# Sheet1.net
KiCad netlist of a schematic drawn in Altium Designer
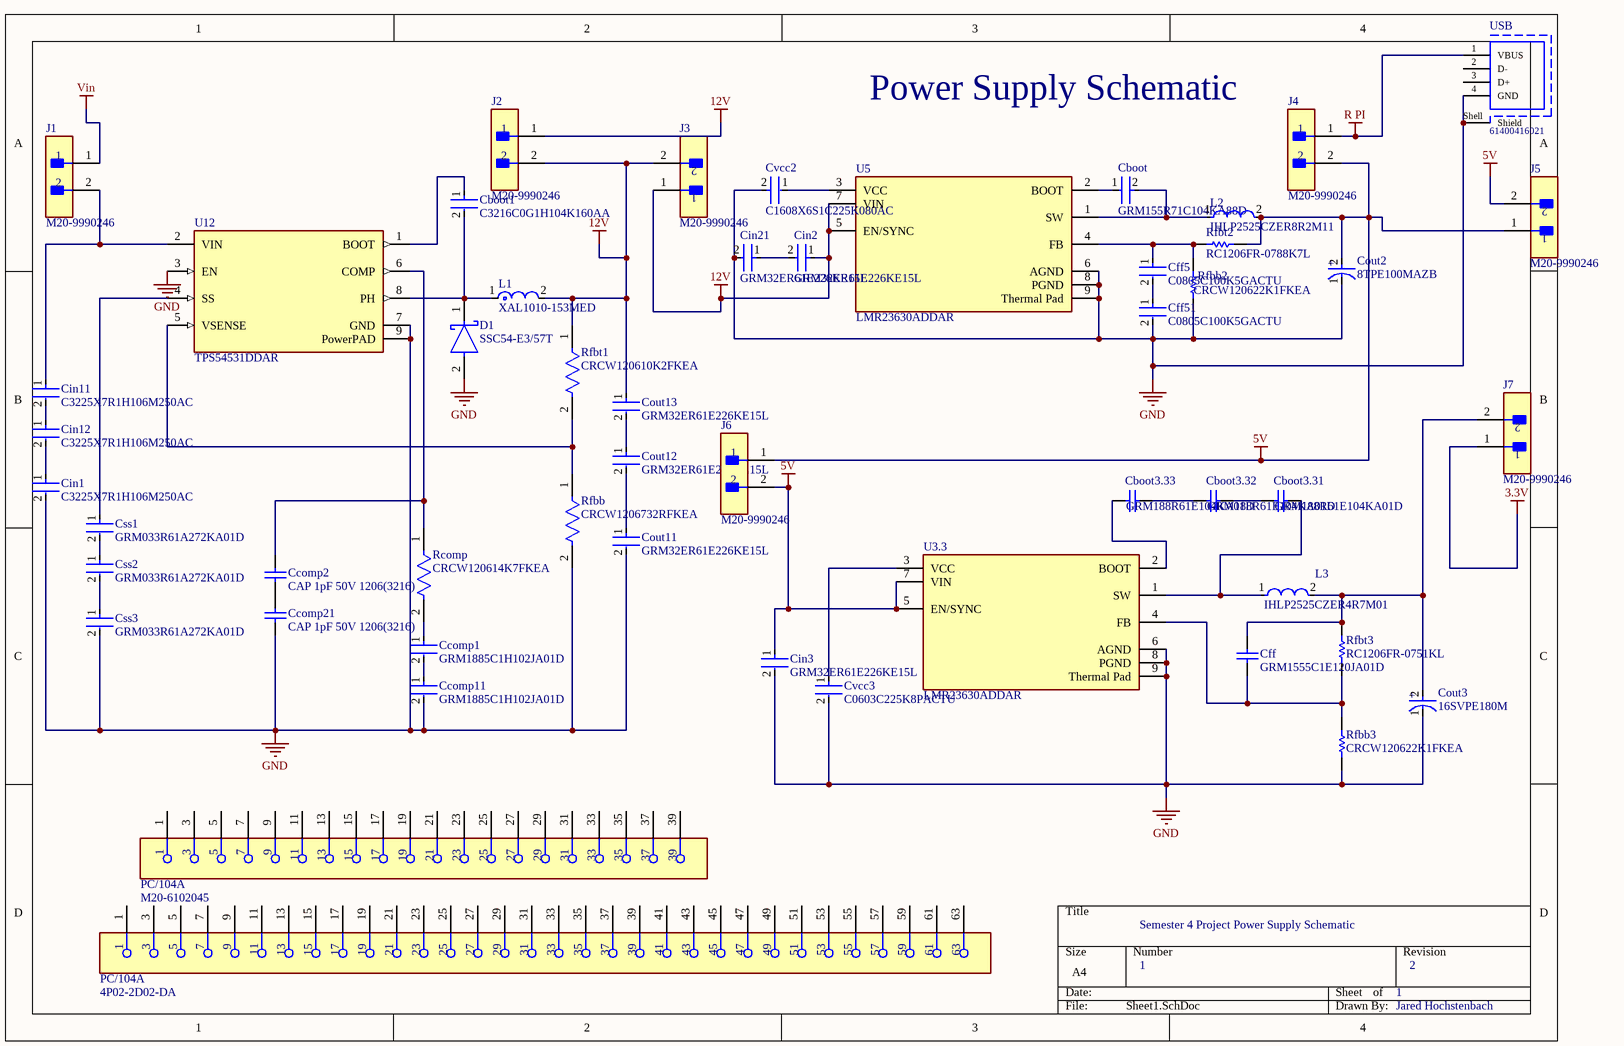
[diagram p0: Sheet1.SchDoc]

(export (version "E")
  (design (tool "Eeschema 10.0.6"))
  (components
    (comp (ref "Cboot")
      (value "GRM155R71C104KA88D")
      (footprint "FP-GRM15-MFG")
      (description "CAP CER 0.1UF 16V X7R 0402")
      (fields
        (field (name "TOLERANCE") "10%")
        (field (name "OCTOPART") "https://octopart.com/grm155r71c104ka88d-murata-196880")
      )
      (libsource (lib "Altium Content Vault") (part "236180d848d6139a670b325ea6854c9"))
    )
    (comp (ref "Cboot1")
      (value "C3216C0G1H104K160AA")
      (footprint "FP-C3216-160-0_2-IPC_C")
      (description "Multilayer Ceramic Capacitors 100nF ±10% 50V C0G SMD 1206")
      (fields (field (name "TOLERANCE") "10%"))
      (libsource (lib "Altium Content Vault") (part "11868f565c42a9108669ba33697ecf6"))
    )
    (comp (ref "Cboot3.31")
      (value "GRM188R61E104KA01D")
      (footprint "CAPC1608X90X35NL10T15")
      (fields (field (name "MANUFACTURER") "Murata"))
      (libsource (lib "Altium Content Vault") (part "CAP"))
    )
    (comp (ref "Cboot3.32")
      (value "GRM188R61E104KA01D")
      (footprint "CAPC1608X90X35NL10T15")
      (fields (field (name "MANUFACTURER") "Murata"))
      (libsource (lib "Altium Content Vault") (part "CAP"))
    )
    (comp (ref "Cboot3.33")
      (value "GRM188R61E104KA01D")
      (footprint "CAPC1608X90X35NL10T15")
      (fields (field (name "MANUFACTURER") "Murata"))
      (libsource (lib "Altium Content Vault") (part "CAP"))
    )
    (comp (ref "Ccomp1")
      (value "GRM1885C1H102JA01D")
      (footprint "FP-GRM188-0_1-e0_2_0_5-IPC_C")
      (description "Chip Multilayer Ceramic Capacitors for General Purpose, 0603, 1000pF, C0G, 30ppm/°C, 5%, 50V")
      (fields (field (name "TOLERANCE") "5%") (field (name "VOLTAGE") "50V"))
      (libsource (lib "Altium Content Vault") (part "11868f565c42a9108669ba33697ecf6"))
    )
    (comp (ref "Ccomp2")
      (value "CAP 1pF 50V 1206(3216)")
      (footprint "CAPC1206(3216)100_N")
      (description "CAP 1pF 50V ±0.25pF 1206 (3216 Metric) Thickness 1mm SMD")
      (fields (field (name "TOLERANCE") "Â±0.25pF"))
      (libsource (lib "Altium Content Vault") (part "CAP"))
    )
    (comp (ref "Ccomp11")
      (value "GRM1885C1H102JA01D")
      (footprint "FP-GRM188-0_1-e0_2_0_5-IPC_C")
      (description "Chip Multilayer Ceramic Capacitors for General Purpose, 0603, 1000pF, C0G, 30ppm/°C, 5%, 50V")
      (fields (field (name "TOLERANCE") "5%") (field (name "VOLTAGE") "50V"))
      (libsource (lib "Altium Content Vault") (part "11868f565c42a9108669ba33697ecf6"))
    )
    (comp (ref "Ccomp21")
      (value "CAP 1pF 50V 1206(3216)")
      (footprint "CAPC1206(3216)100_N")
      (description "CAP 1pF 50V ±0.25pF 1206 (3216 Metric) Thickness 1mm SMD")
      (fields (field (name "TOLERANCE") "Â±0.25pF"))
      (libsource (lib "Altium Content Vault") (part "CAP"))
    )
    (comp (ref "Cff")
      (value "GRM1555C1E120JA01D")
      (footprint "CAPC1005X55X25LL05T10")
      (fields (field (name "MANUFACTURER") "Murata"))
      (libsource (lib "Altium Content Vault") (part "CAP"))
    )
    (comp (ref "Cff5")
      (value "C0805C100K5GACTU")
      (footprint "FP-C0805C-DN-MFG")
      (description "CAP CER 10PF 50V 10% NP0 0805")
      (fields
        (field (name "MANUFACTURER") "KEMET")
        (field (name "OCTOPART") "https://octopart.com/c0805c100k5gactu-kemet-8089747")
      )
      (libsource (lib "Altium Content Vault") (part "b4654b650e69147ec39a6b967a45e02"))
    )
    (comp (ref "Cff51")
      (value "C0805C100K5GACTU")
      (footprint "FP-C0805C-DN-MFG")
      (description "CAP CER 10PF 50V 10% NP0 0805")
      (fields
        (field (name "MANUFACTURER") "KEMET")
        (field (name "OCTOPART") "https://octopart.com/c0805c100k5gactu-kemet-8089747")
      )
      (libsource (lib "Altium Content Vault") (part "b4654b650e69147ec39a6b967a45e02"))
    )
    (comp (ref "Cin1")
      (value "C3225X7R1H106M250AC")
      (footprint "FP-C3225-250-0_4-MFG")
      (description "Multilayer Ceramic Capacitors 10uF ±20% 50V X7R SMD 1210")
      (fields (field (name "TOLERANCE") "20%"))
      (libsource (lib "Altium Content Vault") (part "02cd4be3c70576c341d710602a673aa"))
    )
    (comp (ref "Cin2")
      (value "GRM32ER61E226KE15L")
      (footprint "FP-GRM32-MFG")
      (description "CAP CER 22UF 25V X5R 1210")
      (fields
        (field (name "TOLERANCE") "10%")
        (field (name "MANUFACTURER") "Murata Electronics North America")
      )
      (libsource (lib "Altium Content Vault") (part "11868f565c42a9108669ba33697ecf6"))
    )
    (comp (ref "Cin3")
      (value "GRM32ER61E226KE15L")
      (footprint "FP-GRM32-MFG")
      (description "CAP CER 22UF 25V X5R 1210")
      (fields
        (field (name "TOLERANCE") "10%")
        (field (name "MANUFACTURER") "Murata Electronics North America")
      )
      (libsource (lib "Altium Content Vault") (part "11868f565c42a9108669ba33697ecf6"))
    )
    (comp (ref "Cin11")
      (value "C3225X7R1H106M250AC")
      (footprint "FP-C3225-250-0_4-MFG")
      (description "Multilayer Ceramic Capacitors 10uF ±20% 50V X7R SMD 1210")
      (fields (field (name "TOLERANCE") "20%"))
      (libsource (lib "Altium Content Vault") (part "02cd4be3c70576c341d710602a673aa"))
    )
    (comp (ref "Cin12")
      (value "C3225X7R1H106M250AC")
      (footprint "FP-C3225-250-0_4-MFG")
      (description "Multilayer Ceramic Capacitors 10uF ±20% 50V X7R SMD 1210")
      (fields (field (name "TOLERANCE") "20%"))
      (libsource (lib "Altium Content Vault") (part "02cd4be3c70576c341d710602a673aa"))
    )
    (comp (ref "Cin21")
      (value "GRM32ER61E226KE15L")
      (footprint "FP-GRM32-MFG")
      (description "CAP CER 22UF 25V X5R 1210")
      (fields
        (field (name "TOLERANCE") "10%")
        (field (name "MANUFACTURER") "Murata Electronics North America")
      )
      (libsource (lib "Altium Content Vault") (part "11868f565c42a9108669ba33697ecf6"))
    )
    (comp (ref "Cout2")
      (value "8TPE100MAZB")
      (footprint "FP-POSCAP-B2-MFG")
      (description "Molded Tantalum Polymer Capacitor 100uF 20% 8V life 1000Hours SMD 1411")
      (fields (field (name "TOLERANCE") "20%") (field (name "VOLTAGE") "8V"))
      (libsource (lib "Altium Content Vault") (part "cf48714ba7e38822c1575c7ec0b6d1f"))
    )
    (comp (ref "Cout3")
      (value "16SVPE180M")
      (footprint "FP-OS-CON-SMT-C10-MFG")
      (description "CAP ALUM POLY 180UF 20% 16V SMD")
      (fields (field (name "VOLTAGE") "16V") (field (name "TOLERANCE") "20%"))
      (libsource (lib "Altium Content Vault") (part "203bc49f2ac43e59fd269a8c329ed05"))
    )
    (comp (ref "Cout11")
      (value "GRM32ER61E226KE15L")
      (footprint "FP-GRM32-MFG")
      (description "CAP CER 22UF 25V X5R 1210")
      (fields
        (field (name "TOLERANCE") "10%")
        (field (name "MANUFACTURER") "Murata Electronics North America")
      )
      (libsource (lib "Altium Content Vault") (part "11868f565c42a9108669ba33697ecf6"))
    )
    (comp (ref "Cout12")
      (value "GRM32ER61E226KE15L")
      (footprint "FP-GRM32-MFG")
      (description "CAP CER 22UF 25V X5R 1210")
      (fields
        (field (name "TOLERANCE") "10%")
        (field (name "MANUFACTURER") "Murata Electronics North America")
      )
      (libsource (lib "Altium Content Vault") (part "11868f565c42a9108669ba33697ecf6"))
    )
    (comp (ref "Cout13")
      (value "GRM32ER61E226KE15L")
      (footprint "FP-GRM32-MFG")
      (description "CAP CER 22UF 25V X5R 1210")
      (fields
        (field (name "TOLERANCE") "10%")
        (field (name "MANUFACTURER") "Murata Electronics North America")
      )
      (libsource (lib "Altium Content Vault") (part "11868f565c42a9108669ba33697ecf6"))
    )
    (comp (ref "Css1")
      (value "GRM033R61A272KA01D")
      (footprint "FP-GRM033-0_03-IPC_B")
      (description "Chip Multilayer Ceramic Capacitors for General Purpose, 0201, 2700pF, X5R, 15%, 10%, 10V")
      (fields (field (name "TOLERANCE") "10%"))
      (libsource (lib "Altium Content Vault") (part "b4654b650e69147ec39a6b967a45e02"))
    )
    (comp (ref "Css2")
      (value "GRM033R61A272KA01D")
      (footprint "FP-GRM033-0_03-IPC_B")
      (description "Chip Multilayer Ceramic Capacitors for General Purpose, 0201, 2700pF, X5R, 15%, 10%, 10V")
      (fields (field (name "TOLERANCE") "10%"))
      (libsource (lib "Altium Content Vault") (part "b4654b650e69147ec39a6b967a45e02"))
    )
    (comp (ref "Css3")
      (value "GRM033R61A272KA01D")
      (footprint "FP-GRM033-0_03-IPC_B")
      (description "Chip Multilayer Ceramic Capacitors for General Purpose, 0201, 2700pF, X5R, 15%, 10%, 10V")
      (fields (field (name "TOLERANCE") "10%"))
      (libsource (lib "Altium Content Vault") (part "b4654b650e69147ec39a6b967a45e02"))
    )
    (comp (ref "Cvcc2")
      (value "C1608X6S1C225K080AC")
      (footprint "FP-C1608-080-0_1-IPC_A")
      (description "Multilayer Ceramic Capacitors 2.2μF ±10% 16V X6S SMD 0603")
      (fields (field (name "TOLERANCE") "10%"))
      (libsource (lib "Altium Content Vault") (part "236180d848d6139a670b325ea6854c9"))
    )
    (comp (ref "Cvcc3")
      (value "C0603C225K8PACTU")
      (footprint "FP-C0603C225K8PACTU-MFG")
      (description "CAP CER 2.2UF 10V X5R 0603")
      (fields (field (name "VOLTAGE") "10V") (field (name "TOLERANCE") "10%"))
      (libsource (lib "Altium Content Vault") (part "e9c51b7dd13d4faca003ae77663ab08"))
    )
    (comp (ref "D1")
      (value "SSC54-E3/57T")
      (footprint "FP-95402-MFG")
      (description "DIODE SCHOTTKY 40V 5A DO214AB")
      (fields
        (field (name "OCTOPART") "https://octopart.com/ssc54-e3%2F57t-vishay-39552944")
        (field (name "MANUFACTURER") "Vishay")
      )
      (libsource (lib "Altium Content Vault") (part "1d6ec82d83fb6aee721767c19dac4b9"))
    )
    (comp (ref "J1")
      (value "M20-9990246")
      (footprint "FP-M20-9990246-MFG")
      (description "CONN HEADER VERT 2POS 2.54MM")
      (fields
        (field (name "OCTOPART") "https://octopart.com/m20-9990246-harwin-2590635")
        (field (name "MANUFACTURER") "Harwin")
      )
      (libsource (lib "Altium Content Vault") (part "3bc925449376181038e59eaffc5286c"))
    )
    (comp (ref "J2")
      (value "M20-9990246")
      (footprint "FP-M20-9990246-MFG")
      (description "CONN HEADER VERT 2POS 2.54MM")
      (fields
        (field (name "OCTOPART") "https://octopart.com/m20-9990246-harwin-2590635")
        (field (name "MANUFACTURER") "Harwin")
      )
      (libsource (lib "Altium Content Vault") (part "3bc925449376181038e59eaffc5286c"))
    )
    (comp (ref "J3")
      (value "M20-9990246")
      (footprint "FP-M20-9990246-MFG")
      (description "CONN HEADER VERT 2POS 2.54MM")
      (fields
        (field (name "OCTOPART") "https://octopart.com/m20-9990246-harwin-2590635")
        (field (name "MANUFACTURER") "Harwin")
      )
      (libsource (lib "") (part "3bc925449376181038e59eaffc5286c_1"))
    )
    (comp (ref "J4")
      (value "M20-9990246")
      (footprint "FP-M20-9990246-MFG")
      (description "CONN HEADER VERT 2POS 2.54MM")
      (fields
        (field (name "OCTOPART") "https://octopart.com/m20-9990246-harwin-2590635")
        (field (name "MANUFACTURER") "Harwin")
      )
      (libsource (lib "Altium Content Vault") (part "3bc925449376181038e59eaffc5286c"))
    )
    (comp (ref "J5")
      (value "M20-9990246")
      (footprint "FP-M20-9990246-MFG")
      (description "CONN HEADER VERT 2POS 2.54MM")
      (fields
        (field (name "OCTOPART") "https://octopart.com/m20-9990246-harwin-2590635")
        (field (name "MANUFACTURER") "Harwin")
      )
      (libsource (lib "") (part "3bc925449376181038e59eaffc5286c_1"))
    )
    (comp (ref "J6")
      (value "M20-9990246")
      (footprint "FP-M20-9990246-MFG")
      (description "CONN HEADER VERT 2POS 2.54MM")
      (fields
        (field (name "OCTOPART") "https://octopart.com/m20-9990246-harwin-2590635")
        (field (name "MANUFACTURER") "Harwin")
      )
      (libsource (lib "Altium Content Vault") (part "3bc925449376181038e59eaffc5286c"))
    )
    (comp (ref "J7")
      (value "M20-9990246")
      (footprint "FP-M20-9990246-MFG")
      (description "CONN HEADER VERT 2POS 2.54MM")
      (fields
        (field (name "OCTOPART") "https://octopart.com/m20-9990246-harwin-2590635")
        (field (name "MANUFACTURER") "Harwin")
      )
      (libsource (lib "") (part "3bc925449376181038e59eaffc5286c_1"))
    )
    (comp (ref "L1")
      (value "XAL1010-153MED")
      (footprint "FP-XAL1010-MFG")
      (description "Fixed Inductors 15uH Shld 20% 13.8A 18.6mOhms AECQ2")
      (fields (field (name "TOLERANCE") "20%"))
      (libsource (lib "Altium Content Vault") (part "4cc4b267dca4c8e51f7102f422741d8"))
    )
    (comp (ref "L2")
      (value "IHLP2525CZER8R2M11")
      (footprint "FP-IHLP-2525CZ-FP_2_413x3-MFG")
      (description "Commercial Inductors, Low DCR Series 8.2uH 5A 54.9mΩ 20%")
      (fields (field (name "TOLERANCE") "20%"))
      (libsource (lib "Altium Content Vault") (part "725321dda6339637d4d059423bc1c3c"))
    )
    (comp (ref "L3")
      (value "IHLP2525CZER4R7M01")
      (footprint "FP-IHLP-2525CZ-FP_2_413x3-MFG")
      (description "Commercial Inductors, High Saturation Series 4.7uH 5.5A 40mΩ 20%")
      (fields (field (name "TOLERANCE") "20%"))
      (libsource (lib "Altium Content Vault") (part "725321dda6339637d4d059423bc1c3c"))
    )
    (comp (ref "PC/104")
      (value "4P02-2D02-DA")
      (footprint "FP-4P02-2D02-DA-MFG")
      (description "CONN STKTHRU PC/104 64POS PCB")
      (libsource (lib "Altium Content Vault") (part "e49c52f63edff4b5683a6d6b4db1caa"))
    )
    (comp (ref "Rcomp")
      (value "CRCW120614K7FKEA")
      (footprint "FP-CRCW1206-e3-MFG")
      (description "RES Thick Film, 14.7kΩ, 1%, 0.25W, 100ppm/°C, 1206")
      (fields (field (name "TOLERANCE") "1%"))
      (libsource (lib "Altium Content Vault") (part "1029c3af85768c4190bb7ad29bc67b5"))
    )
    (comp (ref "Rfbb")
      (value "CRCW1206732RFKEA")
      (footprint "FP-CRCW1206-e3-IPC_B")
      (description "RES Thick Film, 732Ω, 1%, 0.25W, 100ppm/°C, 1206")
      (fields (field (name "TOLERANCE") "1%"))
      (libsource (lib "Altium Content Vault") (part "1029c3af85768c4190bb7ad29bc67b5"))
    )
    (comp (ref "Rfbb2")
      (value "CRCW120622K1FKEA")
      (footprint "RESC3216X60X45ML10T20")
      (fields (field (name "MANUFACTURER") "Vishay Dale"))
      (libsource (lib "Altium Content Vault") (part "RES"))
    )
    (comp (ref "Rfbb3")
      (value "CRCW120622K1FKEA")
      (footprint "RESC3216X60X45ML10T20")
      (fields (field (name "MANUFACTURER") "Vishay Dale"))
      (libsource (lib "Altium Content Vault") (part "RES"))
    )
    (comp (ref "Rfbt1")
      (value "CRCW120610K2FKEA")
      (footprint "FP-CRCW1206-e3-MFG")
      (description "RES Thick Film, 10.2kΩ, 1%, 0.25W, 100ppm/°C, 1206")
      (fields (field (name "TOLERANCE") "1%"))
      (libsource (lib "Altium Content Vault") (part "1029c3af85768c4190bb7ad29bc67b5"))
    )
    (comp (ref "Rfbt2")
      (value "RC1206FR-0788K7L")
      (footprint "RESC3116X65X40LL10T20")
      (fields (field (name "MANUFACTURER") "Yageo"))
      (libsource (lib "Altium Content Vault") (part "RES"))
    )
    (comp (ref "Rfbt3")
      (value "RC1206FR-0751KL")
      (footprint "RESC3116X65X40NL10T20")
      (fields (field (name "MANUFACTURER") "Yageo"))
      (libsource (lib "Altium Content Vault") (part "RES"))
    )
    (comp (ref "U3.3")
      (value "LMR23630ADDAR")
      (footprint "FP-DDA0008E-MFG")
      (description "IC REG BUCK ADJUSTABLE 3A 8SOPWR")
      (libsource (lib "Altium Content Vault") (part "58cfab92c18b1e9607657e2a6918072"))
    )
    (comp (ref "U5")
      (value "LMR23630ADDAR")
      (footprint "FP-DDA0008E-MFG")
      (description "IC REG BUCK ADJUSTABLE 3A 8SOPWR")
      (libsource (lib "Altium Content Vault") (part "58cfab92c18b1e9607657e2a6918072"))
    )
    (comp (ref "U12")
      (value "TPS54531DDAR")
      (footprint "FP-DDA0008E-MFG")
      (description "IC REG BUCK ADJUSTABLE 5A 8SOPWR")
      (libsource (lib "Altium Content Vault") (part "0ba9c67d8848e7a3c062535a516a02c"))
    )
    (comp (ref "USB")
      (value "61400416021")
      (footprint "61400416021")
      (description "USB 2.0 Type A Receptacle WR-COM, Horizontal, THT")
      (fields (field (name "MANUFACTURER") "Wurth Elektronik") (field (name "PUBLISHER") "WurthElektronik"))
      (libsource (lib "Altium Content Vault") (part "WE-USB-4-1SHLD"))
    )
  )
  (nets
    (net (code "1") (name "3.3V") (class "Default")
      (node (ref "J7") (pin "1") (pinfunction "1_1") (pintype "passive"))
    )
    (net (code "2") (name "5V") (class "Default")
      (node (ref "Cin3") (pin "1") (pinfunction "1_1") (pintype "passive"))
      (node (ref "Cout2") (pin "2") (pinfunction "A_2") (pintype "passive"))
      (node (ref "J4") (pin "2") (pinfunction "2_2") (pintype "passive"))
      (node (ref "J5") (pin "1") (pinfunction "1_1") (pintype "passive"))
      (node (ref "J5") (pin "2") (pinfunction "2_2") (pintype "passive"))
      (node (ref "J6") (pin "1") (pinfunction "1_1") (pintype "passive"))
      (node (ref "J6") (pin "2") (pinfunction "2_2") (pintype "passive"))
      (node (ref "L2") (pin "2") (pinfunction "2_2") (pintype "passive"))
      (node (ref "Rfbt2") (pin "2") (pinfunction "2_2") (pintype "passive"))
      (node (ref "U3.3") (pin "5") (pinfunction "EN/SYNC_5") (pintype "passive"))
      (node (ref "U3.3") (pin "7") (pinfunction "VIN_7") (pintype "power_in"))
    )
    (net (code "3") (name "12V") (class "Default")
      (node (ref "Cin2") (pin "1") (pinfunction "1_1") (pintype "passive"))
      (node (ref "Cout13") (pin "1") (pinfunction "1_1") (pintype "passive"))
      (node (ref "J2") (pin "1") (pinfunction "1_1") (pintype "passive"))
      (node (ref "J2") (pin "2") (pinfunction "2_2") (pintype "passive"))
      (node (ref "J3") (pin "1") (pinfunction "1_1") (pintype "passive"))
      (node (ref "J3") (pin "2") (pinfunction "2_2") (pintype "passive"))
      (node (ref "L1") (pin "2") (pinfunction "2_2") (pintype "passive"))
      (node (ref "Rfbt1") (pin "1") (pinfunction "1_1") (pintype "passive"))
      (node (ref "U5") (pin "5") (pinfunction "EN/SYNC_5") (pintype "passive"))
      (node (ref "U5") (pin "7") (pinfunction "VIN_7") (pintype "power_in"))
    )
    (net (code "4") (name "GND") (class "Default")
      (node (ref "Ccomp11") (pin "2") (pinfunction "2_2") (pintype "passive"))
      (node (ref "Ccomp21") (pin "1") (pinfunction "1_1") (pintype "passive"))
      (node (ref "Cff51") (pin "2") (pinfunction "2_2") (pintype "passive"))
      (node (ref "Cin1") (pin "2") (pinfunction "2_2") (pintype "passive"))
      (node (ref "Cin21") (pin "2") (pinfunction "2_2") (pintype "passive"))
      (node (ref "Cin3") (pin "2") (pinfunction "2_2") (pintype "passive"))
      (node (ref "Cout11") (pin "2") (pinfunction "2_2") (pintype "passive"))
      (node (ref "Cout2") (pin "1") (pinfunction "C_1") (pintype "passive"))
      (node (ref "Cout3") (pin "1") (pinfunction "C_1") (pintype "passive"))
      (node (ref "Css3") (pin "2") (pinfunction "2_2") (pintype "passive"))
      (node (ref "Cvcc2") (pin "2") (pinfunction "2_2") (pintype "passive"))
      (node (ref "Cvcc3") (pin "2") (pinfunction "2_2") (pintype "passive"))
      (node (ref "D1") (pin "2") (pinfunction "A_2") (pintype "passive"))
      (node (ref "Rfbb") (pin "2") (pinfunction "2_2") (pintype "passive"))
      (node (ref "Rfbb2") (pin "2") (pinfunction "2_2") (pintype "passive"))
      (node (ref "Rfbb3") (pin "1") (pinfunction "1_1") (pintype "passive"))
      (node (ref "U12") (pin "3") (pinfunction "EN_3") (pintype "input"))
      (node (ref "U12") (pin "7") (pinfunction "GND_7") (pintype "power_in"))
      (node (ref "U12") (pin "9") (pinfunction "PowerPAD_9") (pintype "power_in"))
      (node (ref "U3.3") (pin "6") (pinfunction "AGND_6") (pintype "power_in"))
      (node (ref "U3.3") (pin "8") (pinfunction "PGND_8") (pintype "power_in"))
      (node (ref "U3.3") (pin "9") (pinfunction "Thermal_Pad_9") (pintype "power_in"))
      (node (ref "U5") (pin "6") (pinfunction "AGND_6") (pintype "power_in"))
      (node (ref "U5") (pin "8") (pinfunction "PGND_8") (pintype "power_in"))
      (node (ref "U5") (pin "9") (pinfunction "Thermal_Pad_9") (pintype "power_in"))
      (node (ref "USB") (pin "4") (pinfunction "GND_4") (pintype "passive"))
      (node (ref "USB") (pin "Shell") (pinfunction "Shield_Shell") (pintype "passive"))
    )
    (net (code "5") (name "Net-(Cboot3.31-Pad1)") (class "Default")
      (node (ref "Cboot3.31") (pin "1") (pinfunction "1_1") (pintype "passive"))
      (node (ref "Cboot3.32") (pin "2") (pinfunction "2_2") (pintype "passive"))
    )
    (net (code "6") (name "Net-(Cboot3.32-Pad1)") (class "Default")
      (node (ref "Cboot3.32") (pin "1") (pinfunction "1_1") (pintype "passive"))
      (node (ref "Cboot3.33") (pin "2") (pinfunction "2_2") (pintype "passive"))
    )
    (net (code "7") (name "Net-(Ccomp1-Pad1)") (class "Default")
      (node (ref "Ccomp1") (pin "1") (pinfunction "1_1") (pintype "passive"))
      (node (ref "Rcomp") (pin "2") (pinfunction "2_2") (pintype "passive"))
    )
    (net (code "8") (name "Net-(Ccomp1-Pad2)") (class "Default")
      (node (ref "Ccomp1") (pin "2") (pinfunction "2_2") (pintype "passive"))
      (node (ref "Ccomp11") (pin "1") (pinfunction "1_1") (pintype "passive"))
    )
    (net (code "9") (name "Net-(Ccomp2-Pad1)") (class "Default")
      (node (ref "Ccomp2") (pin "1") (pinfunction "1_1") (pintype "passive"))
      (node (ref "Ccomp21") (pin "2") (pinfunction "2_2") (pintype "passive"))
    )
    (net (code "10") (name "Net-(Cff5-Pad2)") (class "Default")
      (node (ref "Cff5") (pin "2") (pinfunction "2_2") (pintype "passive"))
      (node (ref "Cff51") (pin "1") (pinfunction "1_1") (pintype "passive"))
    )
    (net (code "11") (name "Net-(Cin1-Pad1)") (class "Default")
      (node (ref "Cin1") (pin "1") (pinfunction "1_1") (pintype "passive"))
      (node (ref "Cin12") (pin "2") (pinfunction "2_2") (pintype "passive"))
    )
    (net (code "12") (name "Net-(Cin2-Pad2)") (class "Default")
      (node (ref "Cin2") (pin "2") (pinfunction "2_2") (pintype "passive"))
      (node (ref "Cin21") (pin "1") (pinfunction "1_1") (pintype "passive"))
    )
    (net (code "13") (name "Net-(Cin11-Pad2)") (class "Default")
      (node (ref "Cin11") (pin "2") (pinfunction "2_2") (pintype "passive"))
      (node (ref "Cin12") (pin "1") (pinfunction "1_1") (pintype "passive"))
    )
    (net (code "14") (name "Net-(Cout3-A)") (class "Default")
      (node (ref "Cff") (pin "2") (pinfunction "2_2") (pintype "passive"))
      (node (ref "Cout3") (pin "2") (pinfunction "A_2") (pintype "passive"))
      (node (ref "J7") (pin "2") (pinfunction "2_2") (pintype "passive"))
      (node (ref "L3") (pin "2") (pinfunction "2_2") (pintype "passive"))
      (node (ref "Rfbt3") (pin "2") (pinfunction "2_2") (pintype "passive"))
    )
    (net (code "15") (name "Net-(Cout11-Pad1)") (class "Default")
      (node (ref "Cout11") (pin "1") (pinfunction "1_1") (pintype "passive"))
      (node (ref "Cout12") (pin "2") (pinfunction "2_2") (pintype "passive"))
    )
    (net (code "16") (name "Net-(Cout12-Pad1)") (class "Default")
      (node (ref "Cout12") (pin "1") (pinfunction "1_1") (pintype "passive"))
      (node (ref "Cout13") (pin "2") (pinfunction "2_2") (pintype "passive"))
    )
    (net (code "17") (name "Net-(Css1-Pad2)") (class "Default")
      (node (ref "Css1") (pin "2") (pinfunction "2_2") (pintype "passive"))
      (node (ref "Css2") (pin "1") (pinfunction "1_1") (pintype "passive"))
    )
    (net (code "18") (name "Net-(Css2-Pad2)") (class "Default")
      (node (ref "Css2") (pin "2") (pinfunction "2_2") (pintype "passive"))
      (node (ref "Css3") (pin "1") (pinfunction "1_1") (pintype "passive"))
    )
    (net (code "19") (name "Net-(D1-C)") (class "Default")
      (node (ref "Cboot1") (pin "2") (pinfunction "2_2") (pintype "passive"))
      (node (ref "D1") (pin "1") (pinfunction "C_1") (pintype "passive"))
      (node (ref "L1") (pin "1") (pinfunction "1_1") (pintype "passive"))
      (node (ref "U12") (pin "8") (pinfunction "PH_8") (pintype "output"))
    )
    (net (code "20") (name "Net-(U3.3-BOOT)") (class "Default")
      (node (ref "Cboot3.33") (pin "1") (pinfunction "1_1") (pintype "passive"))
      (node (ref "U3.3") (pin "2") (pinfunction "BOOT_2") (pintype "passive"))
    )
    (net (code "21") (name "Net-(U3.3-FB)") (class "Default")
      (node (ref "Cff") (pin "1") (pinfunction "1_1") (pintype "passive"))
      (node (ref "Rfbb3") (pin "2") (pinfunction "2_2") (pintype "passive"))
      (node (ref "Rfbt3") (pin "1") (pinfunction "1_1") (pintype "passive"))
      (node (ref "U3.3") (pin "4") (pinfunction "FB_4") (pintype "passive"))
    )
    (net (code "22") (name "Net-(U3.3-SW)") (class "Default")
      (node (ref "Cboot3.31") (pin "2") (pinfunction "2_2") (pintype "passive"))
      (node (ref "L3") (pin "1") (pinfunction "1_1") (pintype "passive"))
      (node (ref "U3.3") (pin "1") (pinfunction "SW_1") (pintype "passive"))
    )
    (net (code "23") (name "Net-(U3.3-VCC)") (class "Default")
      (node (ref "Cvcc3") (pin "1") (pinfunction "1_1") (pintype "passive"))
      (node (ref "U3.3") (pin "3") (pinfunction "VCC_3") (pintype "power_in"))
    )
    (net (code "24") (name "Net-(U5-BOOT)") (class "Default")
      (node (ref "Cboot") (pin "1") (pinfunction "1_1") (pintype "passive"))
      (node (ref "U5") (pin "2") (pinfunction "BOOT_2") (pintype "passive"))
    )
    (net (code "25") (name "Net-(U5-FB)") (class "Default")
      (node (ref "Cff5") (pin "1") (pinfunction "1_1") (pintype "passive"))
      (node (ref "Rfbb2") (pin "1") (pinfunction "1_1") (pintype "passive"))
      (node (ref "Rfbt2") (pin "1") (pinfunction "1_1") (pintype "passive"))
      (node (ref "U5") (pin "4") (pinfunction "FB_4") (pintype "passive"))
    )
    (net (code "26") (name "Net-(U5-SW)") (class "Default")
      (node (ref "Cboot") (pin "2") (pinfunction "2_2") (pintype "passive"))
      (node (ref "L2") (pin "1") (pinfunction "1_1") (pintype "passive"))
      (node (ref "U5") (pin "1") (pinfunction "SW_1") (pintype "passive"))
    )
    (net (code "27") (name "Net-(U5-VCC)") (class "Default")
      (node (ref "Cvcc2") (pin "1") (pinfunction "1_1") (pintype "passive"))
      (node (ref "U5") (pin "3") (pinfunction "VCC_3") (pintype "power_in"))
    )
    (net (code "28") (name "Net-(U12-BOOT)") (class "Default")
      (node (ref "Cboot1") (pin "1") (pinfunction "1_1") (pintype "passive"))
      (node (ref "U12") (pin "1") (pinfunction "BOOT_1") (pintype "output"))
    )
    (net (code "29") (name "Net-(U12-COMP)") (class "Default")
      (node (ref "Ccomp2") (pin "2") (pinfunction "2_2") (pintype "passive"))
      (node (ref "Rcomp") (pin "1") (pinfunction "1_1") (pintype "passive"))
      (node (ref "U12") (pin "6") (pinfunction "COMP_6") (pintype "output"))
    )
    (net (code "30") (name "Net-(U12-SS)") (class "Default")
      (node (ref "Css1") (pin "1") (pinfunction "1_1") (pintype "passive"))
      (node (ref "U12") (pin "4") (pinfunction "SS_4") (pintype "input"))
    )
    (net (code "31") (name "Net-(U12-VIN)") (class "Default")
      (node (ref "Cin11") (pin "1") (pinfunction "1_1") (pintype "passive"))
      (node (ref "J1") (pin "2") (pinfunction "2_2") (pintype "passive"))
      (node (ref "U12") (pin "2") (pinfunction "VIN_2") (pintype "power_in"))
    )
    (net (code "32") (name "Net-(U12-VSENSE)") (class "Default")
      (node (ref "Rfbb") (pin "1") (pinfunction "1_1") (pintype "passive"))
      (node (ref "Rfbt1") (pin "2") (pinfunction "2_2") (pintype "passive"))
      (node (ref "U12") (pin "5") (pinfunction "VSENSE_5") (pintype "input"))
    )
    (net (code "33") (name "R PI") (class "Default")
      (node (ref "J4") (pin "1") (pinfunction "1_1") (pintype "passive"))
      (node (ref "USB") (pin "1") (pinfunction "VBUS_1") (pintype "passive"))
    )
    (net (code "34") (name "Vin") (class "Default")
      (node (ref "J1") (pin "1") (pinfunction "1_1") (pintype "passive"))
    )
    (net (code "35") (name "unconnected-(PC/104-Pad1)") (class "Default")
      (node (ref "PC/104") (pin "1") (pinfunction "1_1") (pintype "passive"))
    )
    (net (code "36") (name "unconnected-(PC/104-Pad1)_1") (class "Default")
      (node (ref "PC/104") (pin "1") (pinfunction "1_1") (pintype "passive"))
    )
    (net (code "37") (name "unconnected-(PC/104-Pad3)") (class "Default")
      (node (ref "PC/104") (pin "3") (pinfunction "3_3") (pintype "passive"))
    )
    (net (code "38") (name "unconnected-(PC/104-Pad3)_1") (class "Default")
      (node (ref "PC/104") (pin "3") (pinfunction "3_3") (pintype "passive"))
    )
    (net (code "39") (name "unconnected-(PC/104-Pad5)") (class "Default")
      (node (ref "PC/104") (pin "5") (pinfunction "5_5") (pintype "passive"))
    )
    (net (code "40") (name "unconnected-(PC/104-Pad5)_1") (class "Default")
      (node (ref "PC/104") (pin "5") (pinfunction "5_5") (pintype "passive"))
    )
    (net (code "41") (name "unconnected-(PC/104-Pad7)") (class "Default")
      (node (ref "PC/104") (pin "7") (pinfunction "7_7") (pintype "passive"))
    )
    (net (code "42") (name "unconnected-(PC/104-Pad7)_1") (class "Default")
      (node (ref "PC/104") (pin "7") (pinfunction "7_7") (pintype "passive"))
    )
    (net (code "43") (name "unconnected-(PC/104-Pad9)") (class "Default")
      (node (ref "PC/104") (pin "9") (pinfunction "9_9") (pintype "passive"))
    )
    (net (code "44") (name "unconnected-(PC/104-Pad9)_1") (class "Default")
      (node (ref "PC/104") (pin "9") (pinfunction "9_9") (pintype "passive"))
    )
    (net (code "45") (name "unconnected-(PC/104-Pad11)") (class "Default")
      (node (ref "PC/104") (pin "11") (pinfunction "11_11") (pintype "passive"))
    )
    (net (code "46") (name "unconnected-(PC/104-Pad11)_1") (class "Default")
      (node (ref "PC/104") (pin "11") (pinfunction "11_11") (pintype "passive"))
    )
    (net (code "47") (name "unconnected-(PC/104-Pad13)") (class "Default")
      (node (ref "PC/104") (pin "13") (pinfunction "13_13") (pintype "passive"))
    )
    (net (code "48") (name "unconnected-(PC/104-Pad13)_1") (class "Default")
      (node (ref "PC/104") (pin "13") (pinfunction "13_13") (pintype "passive"))
    )
    (net (code "49") (name "unconnected-(PC/104-Pad15)") (class "Default")
      (node (ref "PC/104") (pin "15") (pinfunction "15_15") (pintype "passive"))
    )
    (net (code "50") (name "unconnected-(PC/104-Pad15)_1") (class "Default")
      (node (ref "PC/104") (pin "15") (pinfunction "15_15") (pintype "passive"))
    )
    (net (code "51") (name "unconnected-(PC/104-Pad17)") (class "Default")
      (node (ref "PC/104") (pin "17") (pinfunction "17_17") (pintype "passive"))
    )
    (net (code "52") (name "unconnected-(PC/104-Pad17)_1") (class "Default")
      (node (ref "PC/104") (pin "17") (pinfunction "17_17") (pintype "passive"))
    )
    (net (code "53") (name "unconnected-(PC/104-Pad19)") (class "Default")
      (node (ref "PC/104") (pin "19") (pinfunction "19_19") (pintype "passive"))
    )
    (net (code "54") (name "unconnected-(PC/104-Pad19)_1") (class "Default")
      (node (ref "PC/104") (pin "19") (pinfunction "19_19") (pintype "passive"))
    )
    (net (code "55") (name "unconnected-(PC/104-Pad21)") (class "Default")
      (node (ref "PC/104") (pin "21") (pinfunction "21_21") (pintype "passive"))
    )
    (net (code "56") (name "unconnected-(PC/104-Pad21)_1") (class "Default")
      (node (ref "PC/104") (pin "21") (pinfunction "21_21") (pintype "passive"))
    )
    (net (code "57") (name "unconnected-(PC/104-Pad23)") (class "Default")
      (node (ref "PC/104") (pin "23") (pinfunction "23_23") (pintype "passive"))
    )
    (net (code "58") (name "unconnected-(PC/104-Pad23)_1") (class "Default")
      (node (ref "PC/104") (pin "23") (pinfunction "23_23") (pintype "passive"))
    )
    (net (code "59") (name "unconnected-(PC/104-Pad25)") (class "Default")
      (node (ref "PC/104") (pin "25") (pinfunction "25_25") (pintype "passive"))
    )
    (net (code "60") (name "unconnected-(PC/104-Pad25)_1") (class "Default")
      (node (ref "PC/104") (pin "25") (pinfunction "25_25") (pintype "passive"))
    )
    (net (code "61") (name "unconnected-(PC/104-Pad27)") (class "Default")
      (node (ref "PC/104") (pin "27") (pinfunction "27_27") (pintype "passive"))
    )
    (net (code "62") (name "unconnected-(PC/104-Pad27)_1") (class "Default")
      (node (ref "PC/104") (pin "27") (pinfunction "27_27") (pintype "passive"))
    )
    (net (code "63") (name "unconnected-(PC/104-Pad29)") (class "Default")
      (node (ref "PC/104") (pin "29") (pinfunction "29_29") (pintype "passive"))
    )
    (net (code "64") (name "unconnected-(PC/104-Pad29)_1") (class "Default")
      (node (ref "PC/104") (pin "29") (pinfunction "29_29") (pintype "passive"))
    )
    (net (code "65") (name "unconnected-(PC/104-Pad31)") (class "Default")
      (node (ref "PC/104") (pin "31") (pinfunction "31_31") (pintype "passive"))
    )
    (net (code "66") (name "unconnected-(PC/104-Pad31)_1") (class "Default")
      (node (ref "PC/104") (pin "31") (pinfunction "31_31") (pintype "passive"))
    )
    (net (code "67") (name "unconnected-(PC/104-Pad33)") (class "Default")
      (node (ref "PC/104") (pin "33") (pinfunction "33_33") (pintype "passive"))
    )
    (net (code "68") (name "unconnected-(PC/104-Pad33)_1") (class "Default")
      (node (ref "PC/104") (pin "33") (pinfunction "33_33") (pintype "passive"))
    )
    (net (code "69") (name "unconnected-(PC/104-Pad35)") (class "Default")
      (node (ref "PC/104") (pin "35") (pinfunction "35_35") (pintype "passive"))
    )
    (net (code "70") (name "unconnected-(PC/104-Pad35)_1") (class "Default")
      (node (ref "PC/104") (pin "35") (pinfunction "35_35") (pintype "passive"))
    )
    (net (code "71") (name "unconnected-(PC/104-Pad37)") (class "Default")
      (node (ref "PC/104") (pin "37") (pinfunction "37_37") (pintype "passive"))
    )
    (net (code "72") (name "unconnected-(PC/104-Pad37)_1") (class "Default")
      (node (ref "PC/104") (pin "37") (pinfunction "37_37") (pintype "passive"))
    )
    (net (code "73") (name "unconnected-(PC/104-Pad39)") (class "Default")
      (node (ref "PC/104") (pin "39") (pinfunction "39_39") (pintype "passive"))
    )
    (net (code "74") (name "unconnected-(PC/104-Pad39)_1") (class "Default")
      (node (ref "PC/104") (pin "39") (pinfunction "39_39") (pintype "passive"))
    )
    (net (code "75") (name "unconnected-(PC/104-Pad41)") (class "Default")
      (node (ref "PC/104") (pin "41") (pinfunction "41_41") (pintype "passive"))
    )
    (net (code "76") (name "unconnected-(PC/104-Pad43)") (class "Default")
      (node (ref "PC/104") (pin "43") (pinfunction "43_43") (pintype "passive"))
    )
    (net (code "77") (name "unconnected-(PC/104-Pad45)") (class "Default")
      (node (ref "PC/104") (pin "45") (pinfunction "45_45") (pintype "passive"))
    )
    (net (code "78") (name "unconnected-(PC/104-Pad47)") (class "Default")
      (node (ref "PC/104") (pin "47") (pinfunction "47_47") (pintype "passive"))
    )
    (net (code "79") (name "unconnected-(PC/104-Pad49)") (class "Default")
      (node (ref "PC/104") (pin "49") (pinfunction "49_49") (pintype "passive"))
    )
    (net (code "80") (name "unconnected-(PC/104-Pad51)") (class "Default")
      (node (ref "PC/104") (pin "51") (pinfunction "51_51") (pintype "passive"))
    )
    (net (code "81") (name "unconnected-(PC/104-Pad53)") (class "Default")
      (node (ref "PC/104") (pin "53") (pinfunction "53_53") (pintype "passive"))
    )
    (net (code "82") (name "unconnected-(PC/104-Pad55)") (class "Default")
      (node (ref "PC/104") (pin "55") (pinfunction "55_55") (pintype "passive"))
    )
    (net (code "83") (name "unconnected-(PC/104-Pad57)") (class "Default")
      (node (ref "PC/104") (pin "57") (pinfunction "57_57") (pintype "passive"))
    )
    (net (code "84") (name "unconnected-(PC/104-Pad59)") (class "Default")
      (node (ref "PC/104") (pin "59") (pinfunction "59_59") (pintype "passive"))
    )
    (net (code "85") (name "unconnected-(PC/104-Pad61)") (class "Default")
      (node (ref "PC/104") (pin "61") (pinfunction "61_61") (pintype "passive"))
    )
    (net (code "86") (name "unconnected-(PC/104-Pad63)") (class "Default")
      (node (ref "PC/104") (pin "63") (pinfunction "63_63") (pintype "passive"))
    )
    (net (code "87") (name "unconnected-(USB-D+-Pad3)") (class "Default")
      (node (ref "USB") (pin "3") (pinfunction "D+_3") (pintype "passive"))
    )
    (net (code "88") (name "unconnected-(USB-D--Pad2)") (class "Default")
      (node (ref "USB") (pin "2") (pinfunction "D-_2") (pintype "passive"))
    )
  )
)
